# Genesis_Model1_RGB_LED.net
KiCad netlist of a schematic drawn in EAGLE
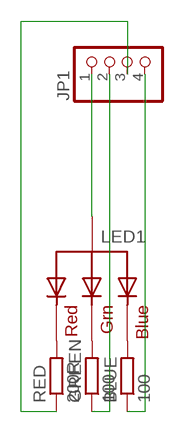
[diagram p0: schematic, sheet 1]

(export (version "E")
  (design (tool "Eeschema 10.0.6"))
  (components
    (comp (ref "BLUE")
      (value "100")
      (footprint "eagle-import:R0805")
      (libsource (lib "eagle-import") (part "R-EU_R0805"))
    )
    (comp (ref "GREEN")
      (value "100")
      (footprint "eagle-import:R0805")
      (libsource (lib "eagle-import") (part "R-EU_R0805"))
    )
    (comp (ref "JP1")
      (value "PINHD-1X04_2.00")
      (footprint "eagle-import:1X04M")
      (libsource (lib "eagle-import") (part "PINHD-1X04_2.00"))
    )
    (comp (ref "LED1")
      (value "RGBLED_CA-5MM")
      (footprint "eagle-import:LED5MMRGB")
      (libsource (lib "eagle-import") (part "RGBLED_CA-5MM"))
    )
    (comp (ref "RED")
      (value "200R")
      (footprint "eagle-import:R0805")
      (libsource (lib "eagle-import") (part "R-EU_R0805"))
    )
  )
  (nets
    (net (code "1") (name "Net-(BLUE-Pad1)") (class "Default")
      (node (ref "BLUE") (pin "1") (pinfunction "1_1") (pintype "passive"))
      (node (ref "JP1") (pin "4") (pinfunction "4_4") (pintype "passive"))
    )
    (net (code "2") (name "Net-(GREEN-Pad1)") (class "Default")
      (node (ref "GREEN") (pin "1") (pinfunction "1_1") (pintype "passive"))
      (node (ref "JP1") (pin "2") (pinfunction "2_2") (pintype "passive"))
    )
    (net (code "3") (name "Net-(JP1-Pad3)") (class "Default")
      (node (ref "JP1") (pin "3") (pinfunction "3_3") (pintype "passive"))
      (node (ref "RED") (pin "1") (pinfunction "1_1") (pintype "passive"))
    )
    (net (code "4") (name "Net-(LED1-BLUE)") (class "Default")
      (node (ref "BLUE") (pin "2") (pinfunction "2_2") (pintype "passive"))
      (node (ref "LED1") (pin "4") (pinfunction "BLUE_4") (pintype "bidirectional"))
    )
    (net (code "5") (name "Net-(LED1-GREEN)") (class "Default")
      (node (ref "GREEN") (pin "2") (pinfunction "2_2") (pintype "passive"))
      (node (ref "LED1") (pin "3") (pinfunction "GREEN_3") (pintype "bidirectional"))
    )
    (net (code "6") (name "Net-(LED1-RED)") (class "Default")
      (node (ref "LED1") (pin "1") (pinfunction "RED_1") (pintype "bidirectional"))
      (node (ref "RED") (pin "2") (pinfunction "2_2") (pintype "passive"))
    )
    (net (code "7") (name "Net-(LED1-VCC)") (class "Default")
      (node (ref "JP1") (pin "1") (pinfunction "1_1") (pintype "passive"))
      (node (ref "LED1") (pin "2") (pinfunction "VCC_2") (pintype "bidirectional"))
    )
  )
)
